# eagle_mini.net
KiCad netlist of a schematic drawn in EAGLE
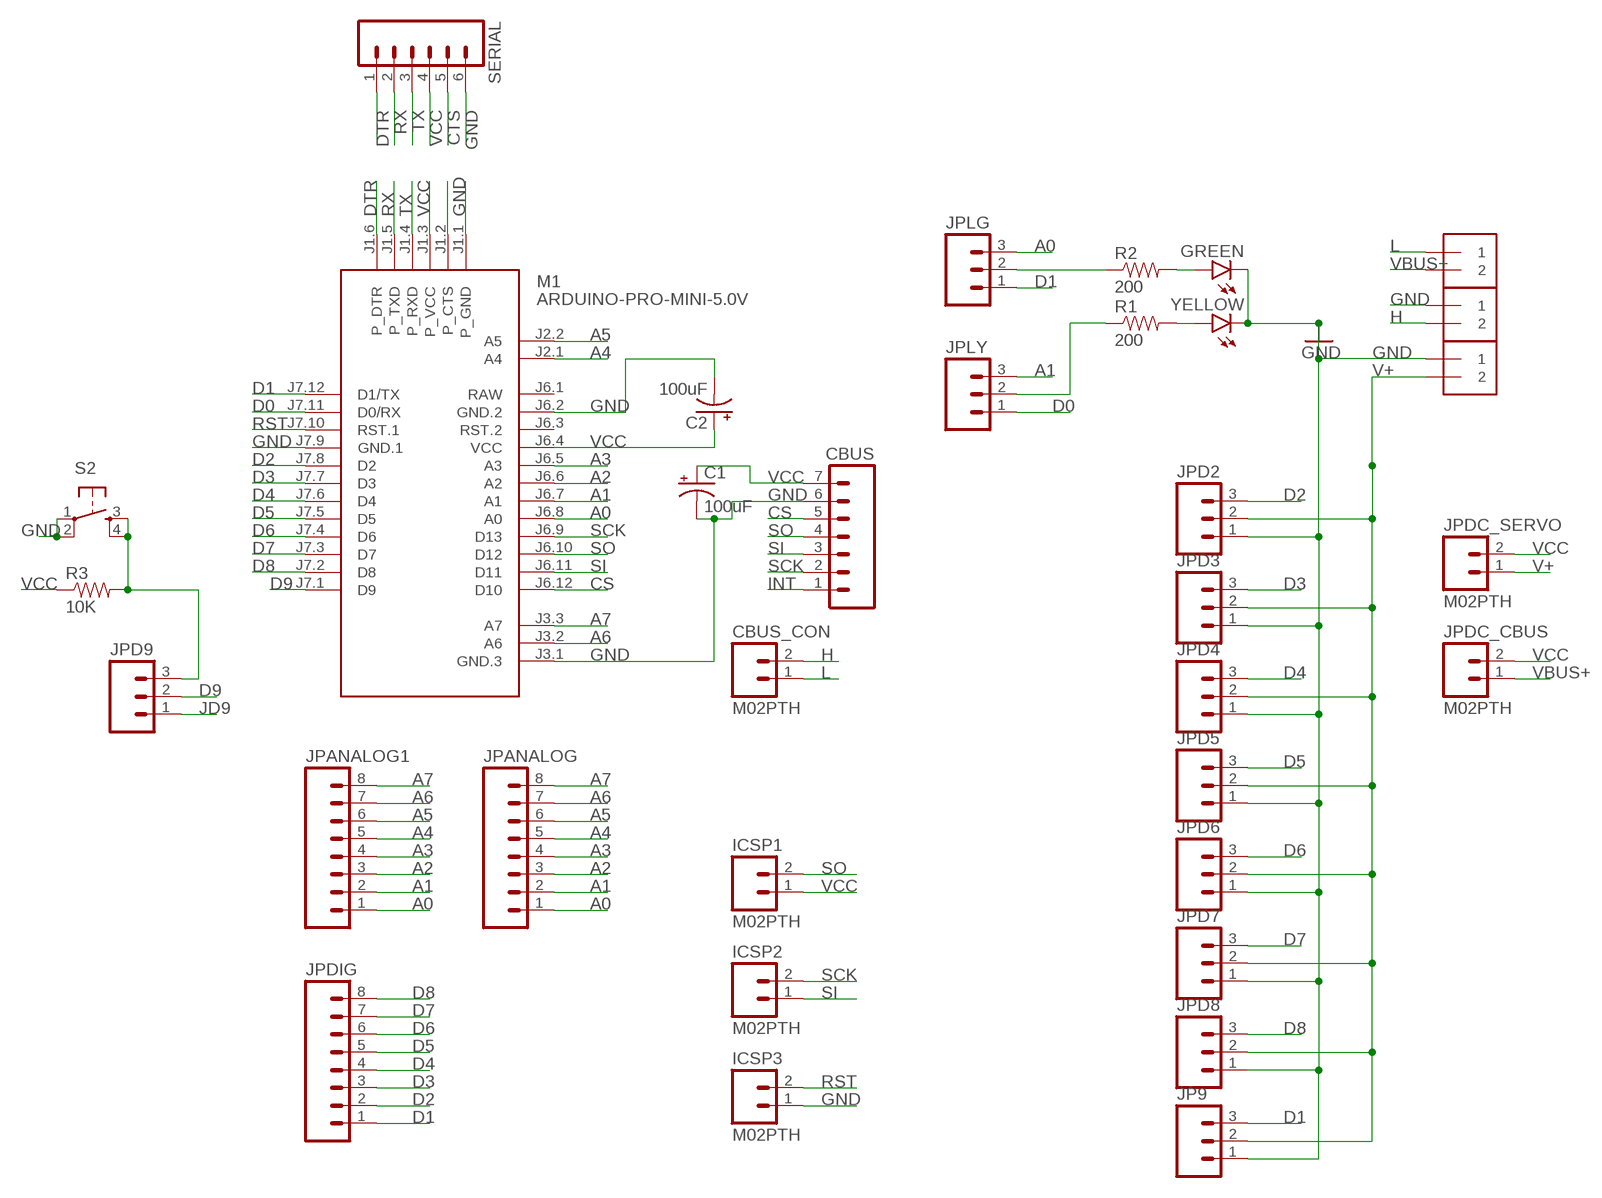
[diagram p0: schematic, sheet 1]

(export (version "E")
  (design (tool "Eeschema 10.0.6"))
  (components
    (comp (ref "C1")
      (value "100uF")
      (footprint "eagle-import:E2,5-6")
      (libsource (lib "eagle-import") (part "CPOL-USE2.5-6"))
    )
    (comp (ref "C2")
      (value "100uF")
      (footprint "eagle-import:E2,5-6")
      (libsource (lib "eagle-import") (part "CPOL-USE2.5-6"))
    )
    (comp (ref "CBUS")
      (value "M07")
      (footprint "eagle-import:1X07")
      (libsource (lib "eagle-import") (part "M07"))
    )
    (comp (ref "CBUS_CON")
      (value "M02PTH")
      (footprint "eagle-import:1X02")
      (libsource (lib "eagle-import") (part "M02PTH"))
    )
    (comp (ref "EXT_VCC")
      (value "1X2-3.5MM")
      (footprint "eagle-import:1X2-3.5MM")
      (libsource (lib "eagle-import") (part "1X2-3.5MM"))
    )
    (comp (ref "GREEN")
      (value "LED-3MM-NO_SILK")
      (footprint "eagle-import:LED3MM-NS")
      (libsource (lib "eagle-import") (part "LED-3MM-NO_SILK"))
    )
    (comp (ref "ICSP1")
      (value "M02PTH")
      (footprint "eagle-import:1X02")
      (libsource (lib "eagle-import") (part "M02PTH"))
    )
    (comp (ref "ICSP2")
      (value "M02PTH")
      (footprint "eagle-import:1X02")
      (libsource (lib "eagle-import") (part "M02PTH"))
    )
    (comp (ref "ICSP3")
      (value "M02PTH")
      (footprint "eagle-import:1X02")
      (libsource (lib "eagle-import") (part "M02PTH"))
    )
    (comp (ref "J1")
      (value "1X2-3.5MM")
      (footprint "eagle-import:1X2-3.5MM")
      (libsource (lib "eagle-import") (part "1X2-3.5MM"))
    )
    (comp (ref "J2")
      (value "1X2-3.5MM")
      (footprint "eagle-import:1X2-3.5MM")
      (libsource (lib "eagle-import") (part "1X2-3.5MM"))
    )
    (comp (ref "JP9")
      (value "M03PTH")
      (footprint "eagle-import:1X03")
      (libsource (lib "eagle-import") (part "M03PTH"))
    )
    (comp (ref "JPANALOG")
      (value "M08")
      (footprint "eagle-import:1X08_ROUND")
      (libsource (lib "eagle-import") (part "M08"))
    )
    (comp (ref "JPANALOG1")
      (value "M08")
      (footprint "eagle-import:1X08_ROUND")
      (libsource (lib "eagle-import") (part "M08"))
    )
    (comp (ref "JPD2")
      (value "M03PTH")
      (footprint "eagle-import:1X03")
      (libsource (lib "eagle-import") (part "M03PTH"))
    )
    (comp (ref "JPD3")
      (value "M03PTH")
      (footprint "eagle-import:1X03")
      (libsource (lib "eagle-import") (part "M03PTH"))
    )
    (comp (ref "JPD4")
      (value "M03PTH")
      (footprint "eagle-import:1X03")
      (libsource (lib "eagle-import") (part "M03PTH"))
    )
    (comp (ref "JPD5")
      (value "M03PTH")
      (footprint "eagle-import:1X03")
      (libsource (lib "eagle-import") (part "M03PTH"))
    )
    (comp (ref "JPD6")
      (value "M03PTH")
      (footprint "eagle-import:1X03")
      (libsource (lib "eagle-import") (part "M03PTH"))
    )
    (comp (ref "JPD7")
      (value "M03PTH")
      (footprint "eagle-import:1X03")
      (libsource (lib "eagle-import") (part "M03PTH"))
    )
    (comp (ref "JPD8")
      (value "M03PTH")
      (footprint "eagle-import:1X03")
      (libsource (lib "eagle-import") (part "M03PTH"))
    )
    (comp (ref "JPD9")
      (value "M03PTH")
      (footprint "eagle-import:1X03")
      (libsource (lib "eagle-import") (part "M03PTH"))
    )
    (comp (ref "JPDC_CBUS")
      (value "M02PTH")
      (footprint "eagle-import:1X02")
      (libsource (lib "eagle-import") (part "M02PTH"))
    )
    (comp (ref "JPDC_SERVO")
      (value "M02PTH")
      (footprint "eagle-import:1X02")
      (libsource (lib "eagle-import") (part "M02PTH"))
    )
    (comp (ref "JPDIG")
      (value "M08")
      (footprint "eagle-import:1X08_ROUND")
      (libsource (lib "eagle-import") (part "M08"))
    )
    (comp (ref "JPLG")
      (value "M03PTH")
      (footprint "eagle-import:1X03")
      (libsource (lib "eagle-import") (part "M03PTH"))
    )
    (comp (ref "JPLY")
      (value "M03PTH")
      (footprint "eagle-import:1X03")
      (libsource (lib "eagle-import") (part "M03PTH"))
    )
    (comp (ref "M1")
      (value "ARDUINO-PRO-MINI-5.0V")
      (footprint "eagle-import:ARDUINO-PRO-MINI")
      (libsource (lib "eagle-import") (part "ARDUINO-PRO-MINI-5.0V"))
    )
    (comp (ref "R1")
      (value "200")
      (footprint "eagle-import:AXIAL-0.3")
      (libsource (lib "eagle-import") (part "RESISTORAXIAL-0.3"))
    )
    (comp (ref "R2")
      (value "200")
      (footprint "eagle-import:AXIAL-0.3")
      (libsource (lib "eagle-import") (part "RESISTORAXIAL-0.3"))
    )
    (comp (ref "R3")
      (value "10K")
      (footprint "eagle-import:AXIAL-0.3")
      (libsource (lib "eagle-import") (part "RESISTORAXIAL-0.3"))
    )
    (comp (ref "S2")
      (value "TAC_SWITCHPTH")
      (footprint "eagle-import:TACTILE-PTH")
      (libsource (lib "eagle-import") (part "TAC_SWITCHPTH"))
    )
    (comp (ref "SERIAL")
      (value "M06SILK_FEMALE_PTH")
      (footprint "eagle-import:1X06")
      (libsource (lib "eagle-import") (part "M06SILK_FEMALE_PTH"))
    )
    (comp (ref "YELLOW")
      (value "LED-3MM-NO_SILK")
      (footprint "eagle-import:LED3MM-NS")
      (libsource (lib "eagle-import") (part "LED-3MM-NO_SILK"))
    )
  )
  (nets
    (net (code "1") (name "/A0") (class "Default")
      (node (ref "JPANALOG") (pin "1") (pinfunction "1_1") (pintype "passive"))
      (node (ref "JPANALOG1") (pin "1") (pinfunction "1_1") (pintype "passive"))
      (node (ref "JPLG") (pin "3") (pinfunction "3_3") (pintype "passive"))
      (node (ref "M1") (pin "J6.8") (pinfunction "A0_J6.8") (pintype "bidirectional"))
    )
    (net (code "2") (name "/A1") (class "Default")
      (node (ref "JPANALOG") (pin "2") (pinfunction "2_2") (pintype "passive"))
      (node (ref "JPANALOG1") (pin "2") (pinfunction "2_2") (pintype "passive"))
      (node (ref "JPLY") (pin "3") (pinfunction "3_3") (pintype "passive"))
      (node (ref "M1") (pin "J6.7") (pinfunction "A1_J6.7") (pintype "bidirectional"))
    )
    (net (code "3") (name "/A2") (class "Default")
      (node (ref "JPANALOG") (pin "3") (pinfunction "3_3") (pintype "passive"))
      (node (ref "JPANALOG1") (pin "3") (pinfunction "3_3") (pintype "passive"))
      (node (ref "M1") (pin "J6.6") (pinfunction "A2_J6.6") (pintype "bidirectional"))
    )
    (net (code "4") (name "/A3") (class "Default")
      (node (ref "JPANALOG") (pin "4") (pinfunction "4_4") (pintype "passive"))
      (node (ref "JPANALOG1") (pin "4") (pinfunction "4_4") (pintype "passive"))
      (node (ref "M1") (pin "J6.5") (pinfunction "A3_J6.5") (pintype "bidirectional"))
    )
    (net (code "5") (name "/A4") (class "Default")
      (node (ref "JPANALOG") (pin "5") (pinfunction "5_5") (pintype "passive"))
      (node (ref "JPANALOG1") (pin "5") (pinfunction "5_5") (pintype "passive"))
      (node (ref "M1") (pin "J2.1") (pinfunction "A4_J2.1") (pintype "bidirectional"))
    )
    (net (code "6") (name "/A5") (class "Default")
      (node (ref "JPANALOG") (pin "6") (pinfunction "6_6") (pintype "passive"))
      (node (ref "JPANALOG1") (pin "6") (pinfunction "6_6") (pintype "passive"))
      (node (ref "M1") (pin "J2.2") (pinfunction "A5_J2.2") (pintype "bidirectional"))
    )
    (net (code "7") (name "/A6") (class "Default")
      (node (ref "JPANALOG") (pin "7") (pinfunction "7_7") (pintype "passive"))
      (node (ref "JPANALOG1") (pin "7") (pinfunction "7_7") (pintype "passive"))
      (node (ref "M1") (pin "J3.2") (pinfunction "A6_J3.2") (pintype "bidirectional"))
    )
    (net (code "8") (name "/A7") (class "Default")
      (node (ref "JPANALOG") (pin "8") (pinfunction "8_8") (pintype "passive"))
      (node (ref "JPANALOG1") (pin "8") (pinfunction "8_8") (pintype "passive"))
      (node (ref "M1") (pin "J3.3") (pinfunction "A7_J3.3") (pintype "bidirectional"))
    )
    (net (code "9") (name "/CS") (class "Default")
      (node (ref "CBUS") (pin "5") (pinfunction "5_5") (pintype "passive"))
      (node (ref "M1") (pin "J6.12") (pinfunction "D10_J6.12") (pintype "bidirectional"))
    )
    (net (code "10") (name "/CTS") (class "Default")
      (node (ref "SERIAL") (pin "5") (pinfunction "5_5") (pintype "passive"))
    )
    (net (code "11") (name "/D0") (class "Default")
      (node (ref "JPLY") (pin "1") (pinfunction "1_1") (pintype "passive"))
      (node (ref "M1") (pin "J7.11") (pinfunction "D0/RX_J7.11") (pintype "bidirectional"))
    )
    (net (code "12") (name "/D1") (class "Default")
      (node (ref "JP9") (pin "3") (pinfunction "3_3") (pintype "passive"))
      (node (ref "JPDIG") (pin "1") (pinfunction "1_1") (pintype "passive"))
      (node (ref "JPLG") (pin "1") (pinfunction "1_1") (pintype "passive"))
      (node (ref "M1") (pin "J7.12") (pinfunction "D1/TX_J7.12") (pintype "bidirectional"))
    )
    (net (code "13") (name "/D2") (class "Default")
      (node (ref "JPD2") (pin "3") (pinfunction "3_3") (pintype "passive"))
      (node (ref "JPDIG") (pin "2") (pinfunction "2_2") (pintype "passive"))
      (node (ref "M1") (pin "J7.8") (pinfunction "D2_J7.8") (pintype "bidirectional"))
    )
    (net (code "14") (name "/D3") (class "Default")
      (node (ref "JPD3") (pin "3") (pinfunction "3_3") (pintype "passive"))
      (node (ref "JPDIG") (pin "3") (pinfunction "3_3") (pintype "passive"))
      (node (ref "M1") (pin "J7.7") (pinfunction "D3_J7.7") (pintype "bidirectional"))
    )
    (net (code "15") (name "/D4") (class "Default")
      (node (ref "JPD4") (pin "3") (pinfunction "3_3") (pintype "passive"))
      (node (ref "JPDIG") (pin "4") (pinfunction "4_4") (pintype "passive"))
      (node (ref "M1") (pin "J7.6") (pinfunction "D4_J7.6") (pintype "bidirectional"))
    )
    (net (code "16") (name "/D5") (class "Default")
      (node (ref "JPD5") (pin "3") (pinfunction "3_3") (pintype "passive"))
      (node (ref "JPDIG") (pin "5") (pinfunction "5_5") (pintype "passive"))
      (node (ref "M1") (pin "J7.5") (pinfunction "D5_J7.5") (pintype "bidirectional"))
    )
    (net (code "17") (name "/D6") (class "Default")
      (node (ref "JPD6") (pin "3") (pinfunction "3_3") (pintype "passive"))
      (node (ref "JPDIG") (pin "6") (pinfunction "6_6") (pintype "passive"))
      (node (ref "M1") (pin "J7.4") (pinfunction "D6_J7.4") (pintype "bidirectional"))
    )
    (net (code "18") (name "/D7") (class "Default")
      (node (ref "JPD7") (pin "3") (pinfunction "3_3") (pintype "passive"))
      (node (ref "JPDIG") (pin "7") (pinfunction "7_7") (pintype "passive"))
      (node (ref "M1") (pin "J7.3") (pinfunction "D7_J7.3") (pintype "bidirectional"))
    )
    (net (code "19") (name "/D8") (class "Default")
      (node (ref "JPD8") (pin "3") (pinfunction "3_3") (pintype "passive"))
      (node (ref "JPDIG") (pin "8") (pinfunction "8_8") (pintype "passive"))
      (node (ref "M1") (pin "J7.2") (pinfunction "D8_J7.2") (pintype "bidirectional"))
    )
    (net (code "20") (name "/D9") (class "Default")
      (node (ref "JPD9") (pin "2") (pinfunction "2_2") (pintype "passive"))
      (node (ref "M1") (pin "J7.1") (pinfunction "D9_J7.1") (pintype "bidirectional"))
    )
    (net (code "21") (name "/DTR") (class "Default")
      (node (ref "M1") (pin "J1.6") (pinfunction "P_DTR_J1.6") (pintype "bidirectional"))
      (node (ref "SERIAL") (pin "1") (pinfunction "1_1") (pintype "passive"))
    )
    (net (code "22") (name "/H") (class "Default")
      (node (ref "CBUS_CON") (pin "2") (pinfunction "2_2") (pintype "passive"))
      (node (ref "J1") (pin "2") (pinfunction "2_2") (pintype "passive"))
    )
    (net (code "23") (name "/INT") (class "Default")
      (node (ref "CBUS") (pin "1") (pinfunction "1_1") (pintype "passive"))
    )
    (net (code "24") (name "/JD9") (class "Default")
      (node (ref "JPD9") (pin "1") (pinfunction "1_1") (pintype "passive"))
    )
    (net (code "25") (name "/L") (class "Default")
      (node (ref "CBUS_CON") (pin "1") (pinfunction "1_1") (pintype "passive"))
      (node (ref "J2") (pin "1") (pinfunction "1_1") (pintype "passive"))
    )
    (net (code "26") (name "/RAW") (class "Default")
      (node (ref "M1") (pin "J6.1") (pinfunction "RAW_J6.1") (pintype "power_in"))
    )
    (net (code "27") (name "/RST") (class "Default")
      (node (ref "ICSP3") (pin "2") (pinfunction "2_2") (pintype "passive"))
      (node (ref "M1") (pin "J7.10") (pinfunction "RST.1_J7.10") (pintype "bidirectional"))
    )
    (net (code "28") (name "/RX") (class "Default")
      (node (ref "M1") (pin "J1.5") (pinfunction "P_TXD_J1.5") (pintype "bidirectional"))
      (node (ref "SERIAL") (pin "2") (pinfunction "2_2") (pintype "passive"))
    )
    (net (code "29") (name "/SCK") (class "Default")
      (node (ref "CBUS") (pin "2") (pinfunction "2_2") (pintype "passive"))
      (node (ref "ICSP2") (pin "2") (pinfunction "2_2") (pintype "passive"))
      (node (ref "M1") (pin "J6.9") (pinfunction "D13_J6.9") (pintype "bidirectional"))
    )
    (net (code "30") (name "/SI") (class "Default")
      (node (ref "CBUS") (pin "3") (pinfunction "3_3") (pintype "passive"))
      (node (ref "ICSP2") (pin "1") (pinfunction "1_1") (pintype "passive"))
      (node (ref "M1") (pin "J6.11") (pinfunction "D11_J6.11") (pintype "bidirectional"))
    )
    (net (code "31") (name "/SO") (class "Default")
      (node (ref "CBUS") (pin "4") (pinfunction "4_4") (pintype "passive"))
      (node (ref "ICSP1") (pin "2") (pinfunction "2_2") (pintype "passive"))
      (node (ref "M1") (pin "J6.10") (pinfunction "D12_J6.10") (pintype "bidirectional"))
    )
    (net (code "32") (name "/TX") (class "Default")
      (node (ref "M1") (pin "J1.4") (pinfunction "P_RXD_J1.4") (pintype "bidirectional"))
      (node (ref "SERIAL") (pin "3") (pinfunction "3_3") (pintype "passive"))
    )
    (net (code "33") (name "/V+") (class "Default")
      (node (ref "EXT_VCC") (pin "2") (pinfunction "2_2") (pintype "passive"))
      (node (ref "JP9") (pin "2") (pinfunction "2_2") (pintype "passive"))
      (node (ref "JPD2") (pin "2") (pinfunction "2_2") (pintype "passive"))
      (node (ref "JPD3") (pin "2") (pinfunction "2_2") (pintype "passive"))
      (node (ref "JPD4") (pin "2") (pinfunction "2_2") (pintype "passive"))
      (node (ref "JPD5") (pin "2") (pinfunction "2_2") (pintype "passive"))
      (node (ref "JPD6") (pin "2") (pinfunction "2_2") (pintype "passive"))
      (node (ref "JPD7") (pin "2") (pinfunction "2_2") (pintype "passive"))
      (node (ref "JPD8") (pin "2") (pinfunction "2_2") (pintype "passive"))
      (node (ref "JPDC_SERVO") (pin "1") (pinfunction "1_1") (pintype "passive"))
    )
    (net (code "34") (name "/VBUS+") (class "Default")
      (node (ref "J2") (pin "2") (pinfunction "2_2") (pintype "passive"))
      (node (ref "JPDC_CBUS") (pin "1") (pinfunction "1_1") (pintype "passive"))
    )
    (net (code "35") (name "/VCC") (class "Default")
      (node (ref "C1") (pin "+") (pinfunction "+_+") (pintype "passive"))
      (node (ref "C2") (pin "+") (pinfunction "+_+") (pintype "passive"))
      (node (ref "CBUS") (pin "7") (pinfunction "7_7") (pintype "passive"))
      (node (ref "ICSP1") (pin "1") (pinfunction "1_1") (pintype "passive"))
      (node (ref "JPDC_CBUS") (pin "2") (pinfunction "2_2") (pintype "passive"))
      (node (ref "JPDC_SERVO") (pin "2") (pinfunction "2_2") (pintype "passive"))
      (node (ref "M1") (pin "J1.3") (pinfunction "P_VCC_J1.3") (pintype "bidirectional"))
      (node (ref "M1") (pin "J6.4") (pinfunction "VCC_J6.4") (pintype "power_in"))
      (node (ref "R3") (pin "P$1") (pinfunction "1_P$1") (pintype "passive"))
      (node (ref "SERIAL") (pin "4") (pinfunction "4_4") (pintype "passive"))
    )
    (net (code "36") (name "GND") (class "Default")
      (node (ref "C1") (pin "-") (pinfunction "-_-") (pintype "passive"))
      (node (ref "C2") (pin "-") (pinfunction "-_-") (pintype "passive"))
      (node (ref "CBUS") (pin "6") (pinfunction "6_6") (pintype "passive"))
      (node (ref "EXT_VCC") (pin "1") (pinfunction "1_1") (pintype "passive"))
      (node (ref "GREEN") (pin "K") (pinfunction "C_K") (pintype "passive"))
      (node (ref "ICSP3") (pin "1") (pinfunction "1_1") (pintype "passive"))
      (node (ref "J1") (pin "1") (pinfunction "1_1") (pintype "passive"))
      (node (ref "JP9") (pin "1") (pinfunction "1_1") (pintype "passive"))
      (node (ref "JPD2") (pin "1") (pinfunction "1_1") (pintype "passive"))
      (node (ref "JPD3") (pin "1") (pinfunction "1_1") (pintype "passive"))
      (node (ref "JPD4") (pin "1") (pinfunction "1_1") (pintype "passive"))
      (node (ref "JPD5") (pin "1") (pinfunction "1_1") (pintype "passive"))
      (node (ref "JPD6") (pin "1") (pinfunction "1_1") (pintype "passive"))
      (node (ref "JPD7") (pin "1") (pinfunction "1_1") (pintype "passive"))
      (node (ref "JPD8") (pin "1") (pinfunction "1_1") (pintype "passive"))
      (node (ref "M1") (pin "J1.1") (pinfunction "P_GND_J1.1") (pintype "bidirectional"))
      (node (ref "M1") (pin "J3.1") (pinfunction "GND.3_J3.1") (pintype "bidirectional"))
      (node (ref "M1") (pin "J6.2") (pinfunction "GND.2_J6.2") (pintype "power_in"))
      (node (ref "M1") (pin "J7.9") (pinfunction "GND.1_J7.9") (pintype "power_in"))
      (node (ref "S2") (pin "1") (pinfunction "1_1") (pintype "passive"))
      (node (ref "S2") (pin "2") (pinfunction "2_2") (pintype "passive"))
      (node (ref "SERIAL") (pin "6") (pinfunction "6_6") (pintype "passive"))
      (node (ref "YELLOW") (pin "K") (pinfunction "C_K") (pintype "passive"))
    )
    (net (code "37") (name "Net-(R1-1)") (class "Default")
      (node (ref "JPLY") (pin "2") (pinfunction "2_2") (pintype "passive"))
      (node (ref "R1") (pin "P$1") (pinfunction "1_P$1") (pintype "passive"))
    )
    (net (code "38") (name "Net-(R1-2)") (class "Default")
      (node (ref "R1") (pin "P$2") (pinfunction "2_P$2") (pintype "passive"))
      (node (ref "YELLOW") (pin "A") (pinfunction "A_A") (pintype "passive"))
    )
    (net (code "39") (name "Net-(R2-1)") (class "Default")
      (node (ref "JPLG") (pin "2") (pinfunction "2_2") (pintype "passive"))
      (node (ref "R2") (pin "P$1") (pinfunction "1_P$1") (pintype "passive"))
    )
    (net (code "40") (name "Net-(R2-2)") (class "Default")
      (node (ref "GREEN") (pin "A") (pinfunction "A_A") (pintype "passive"))
      (node (ref "R2") (pin "P$2") (pinfunction "2_P$2") (pintype "passive"))
    )
    (net (code "41") (name "Net-(R3-2)") (class "Default")
      (node (ref "JPD9") (pin "3") (pinfunction "3_3") (pintype "passive"))
      (node (ref "R3") (pin "P$2") (pinfunction "2_P$2") (pintype "passive"))
      (node (ref "S2") (pin "3") (pinfunction "3_3") (pintype "passive"))
      (node (ref "S2") (pin "4") (pinfunction "4_4") (pintype "passive"))
    )
    (net (code "42") (name "unconnected-(M1-P_CTS-PadJ1.2)") (class "Default")
      (node (ref "M1") (pin "J1.2") (pinfunction "P_CTS_J1.2") (pintype "bidirectional"))
    )
    (net (code "43") (name "unconnected-(M1-RST.2-PadJ6.3)") (class "Default")
      (node (ref "M1") (pin "J6.3") (pinfunction "RST.2_J6.3") (pintype "bidirectional"))
    )
  )
)
